# iridia-tam-main-board.net
KiCad netlist of a schematic drawn in EAGLE
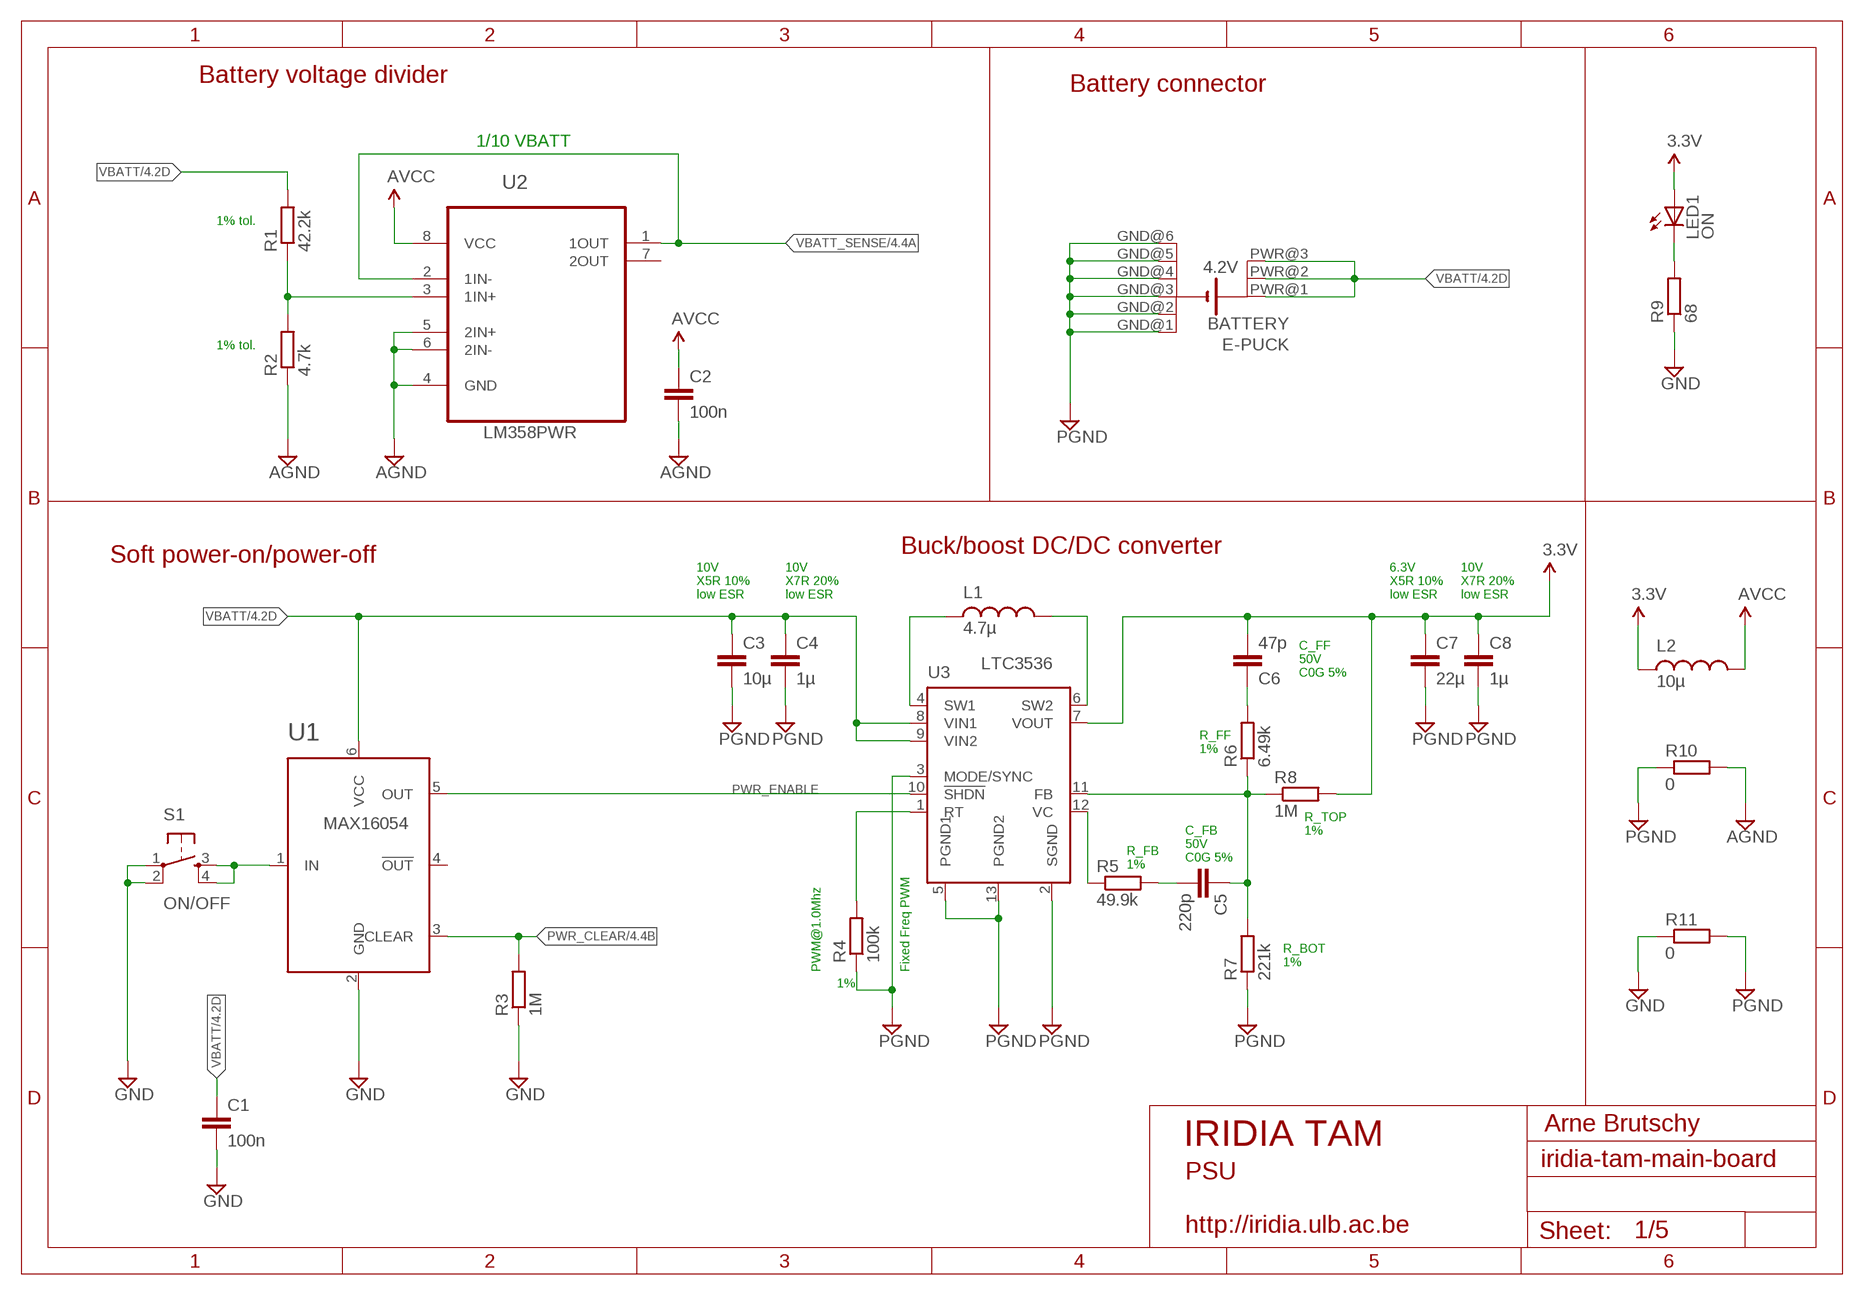
[diagram p0: schematic, sheet 1]
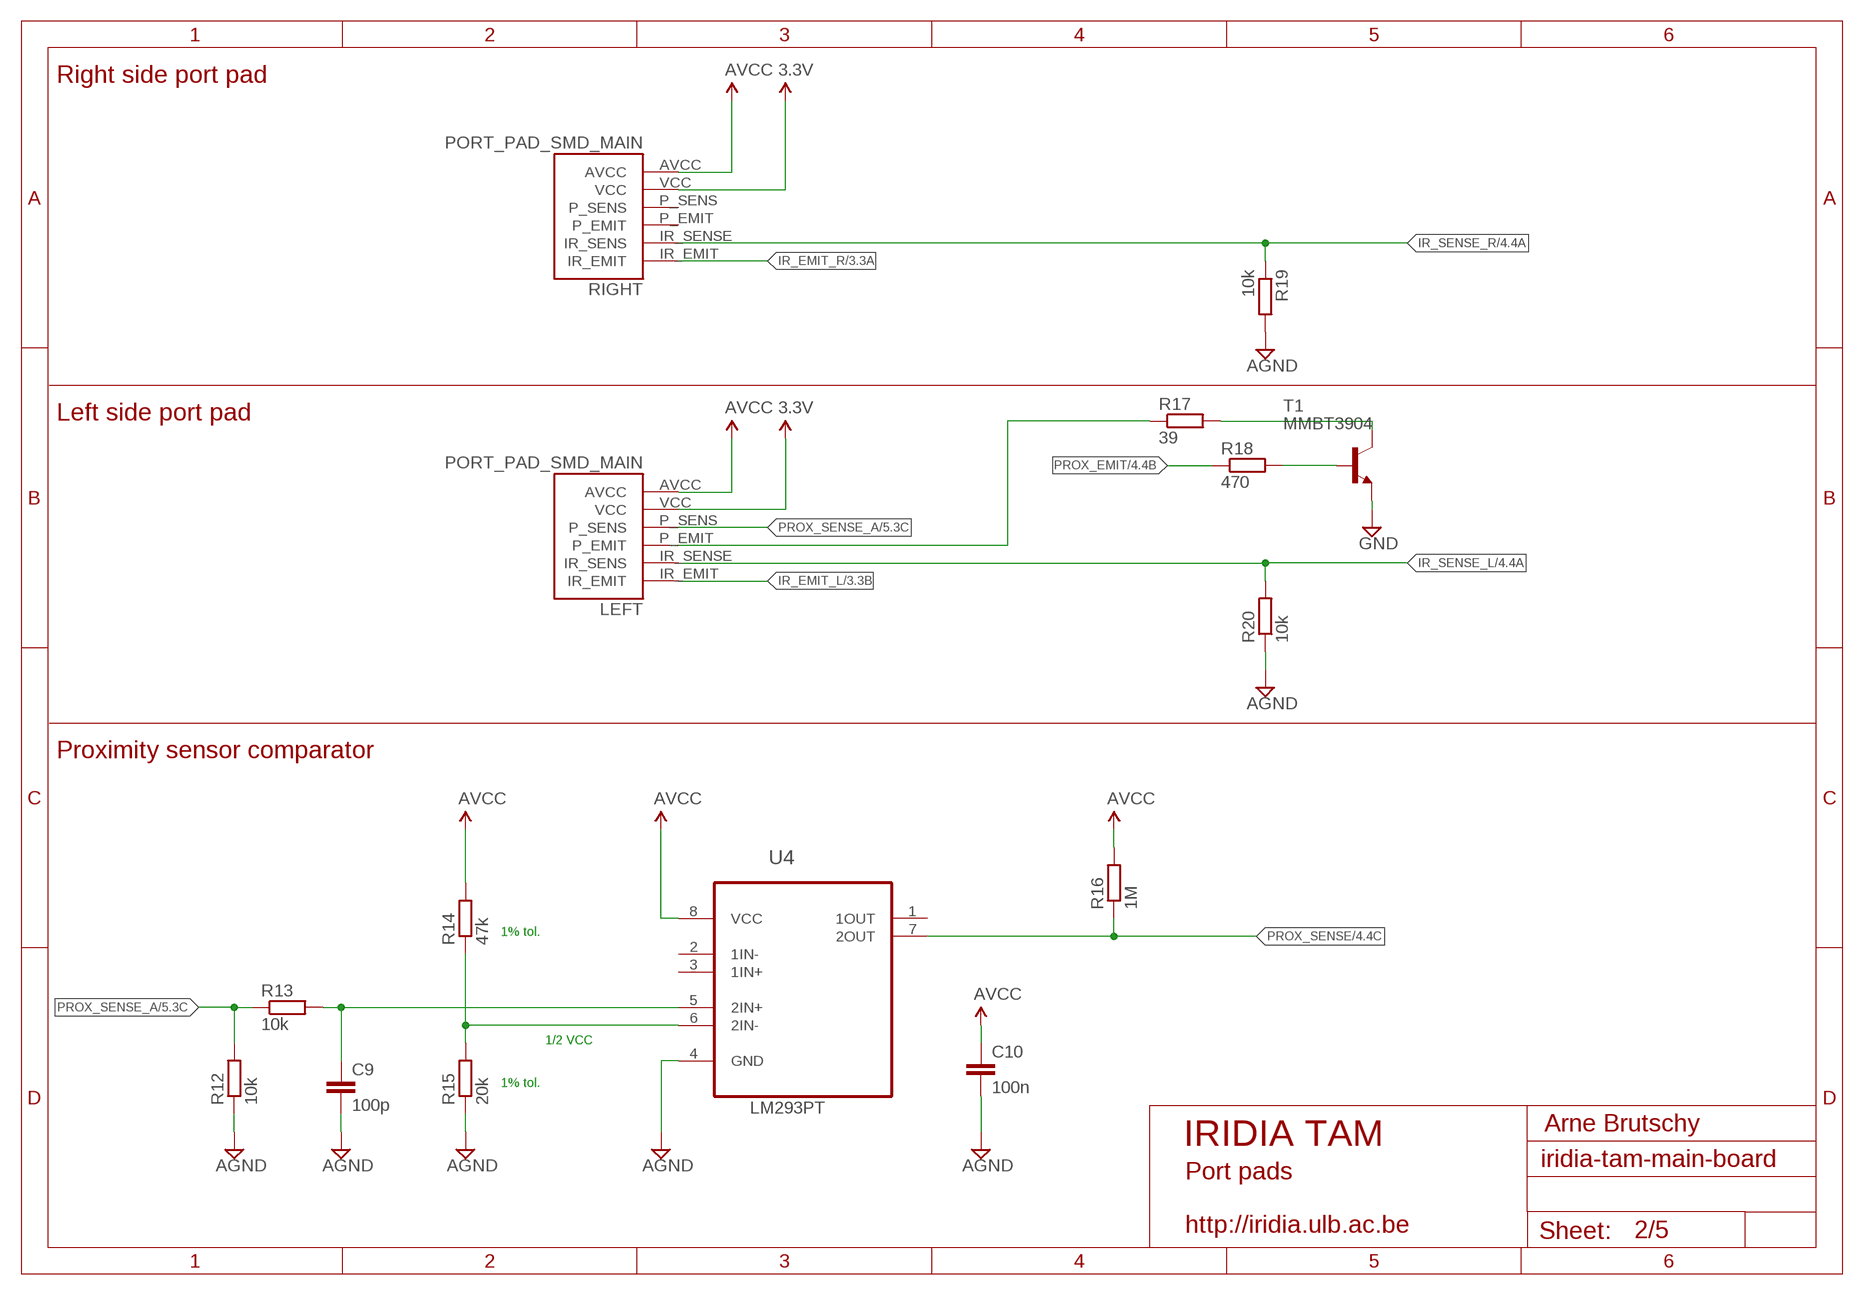
[diagram p1: schematic, sheet 2]
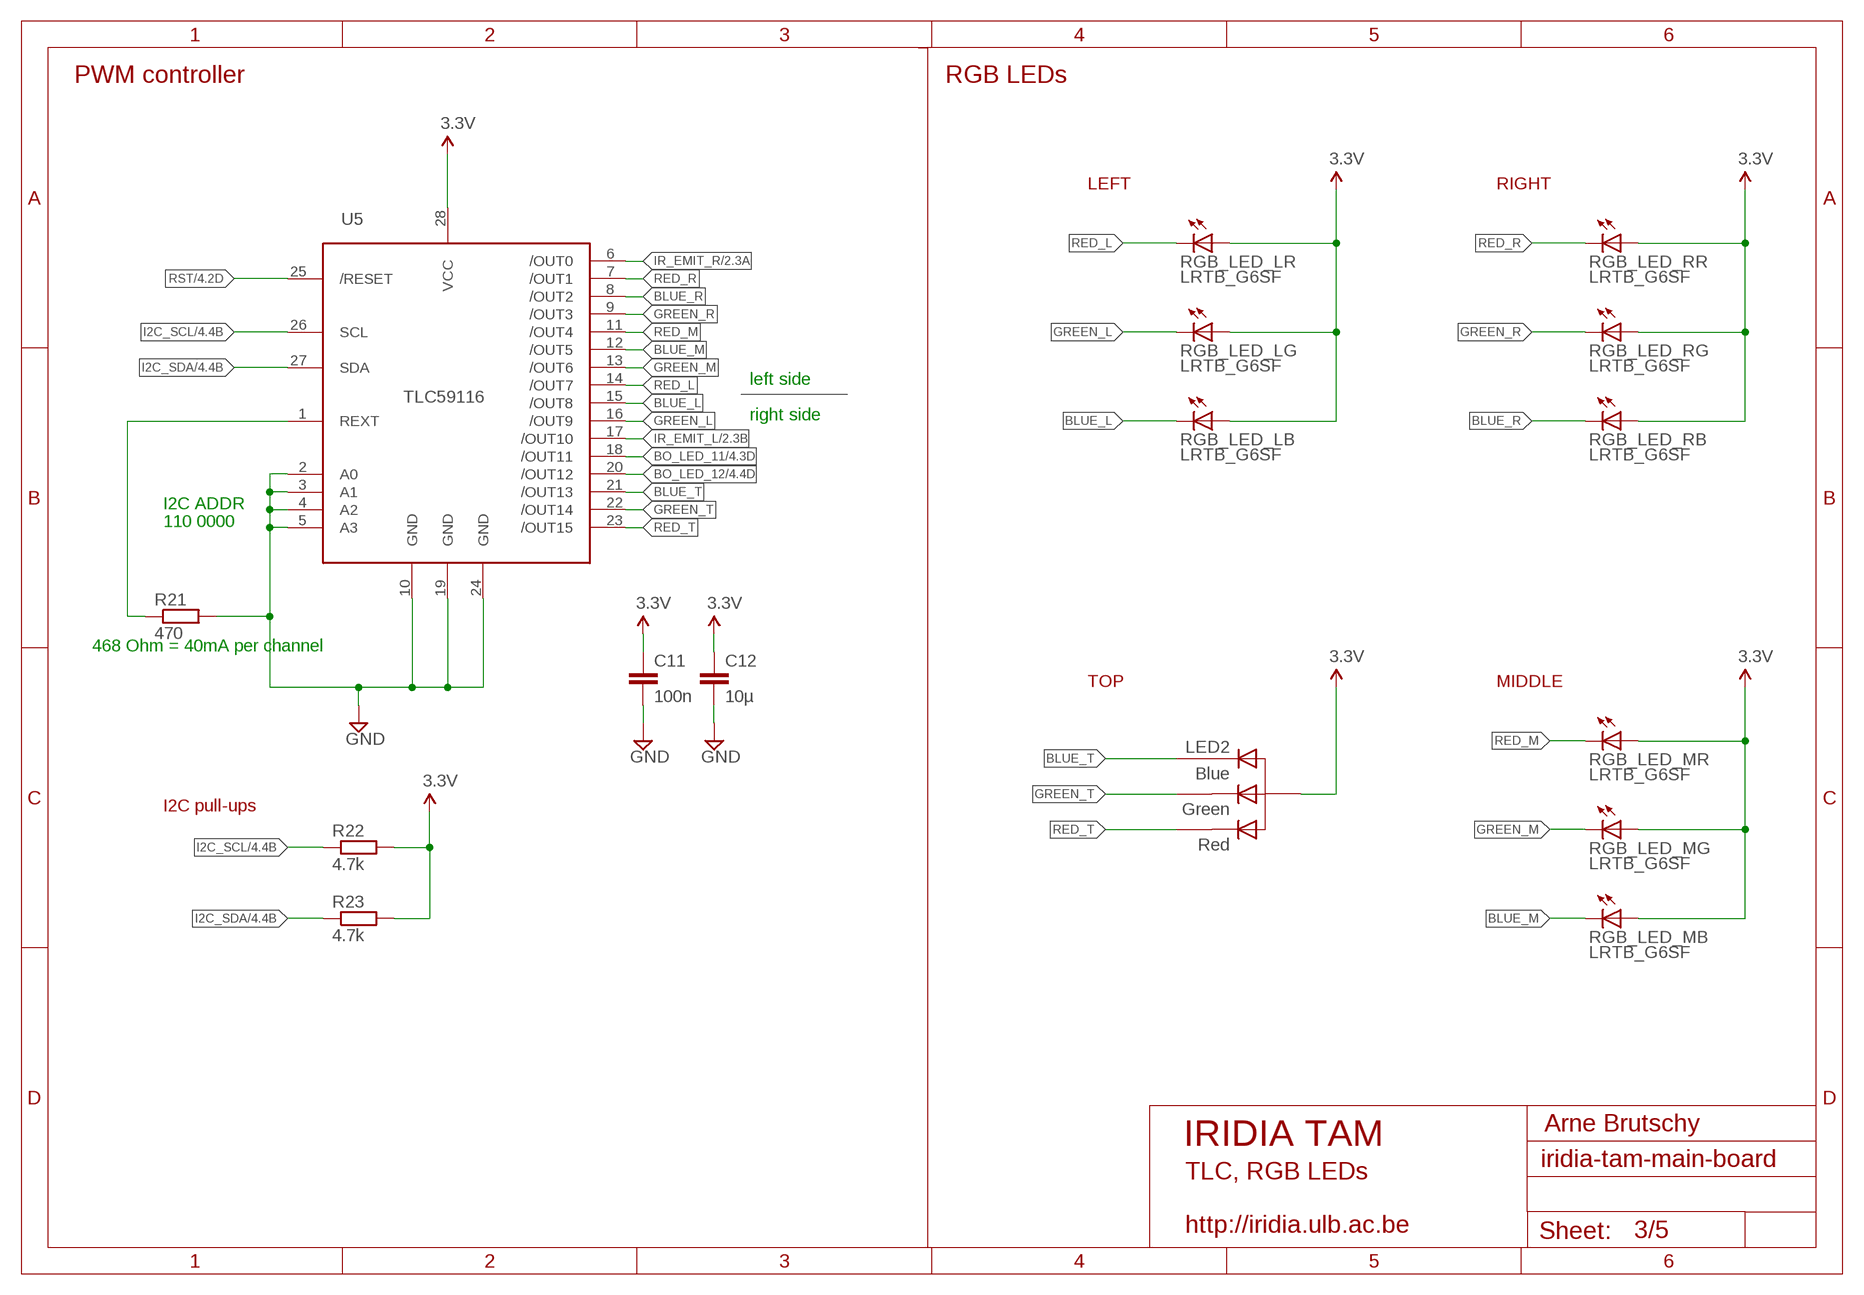
[diagram p2: schematic, sheet 3]
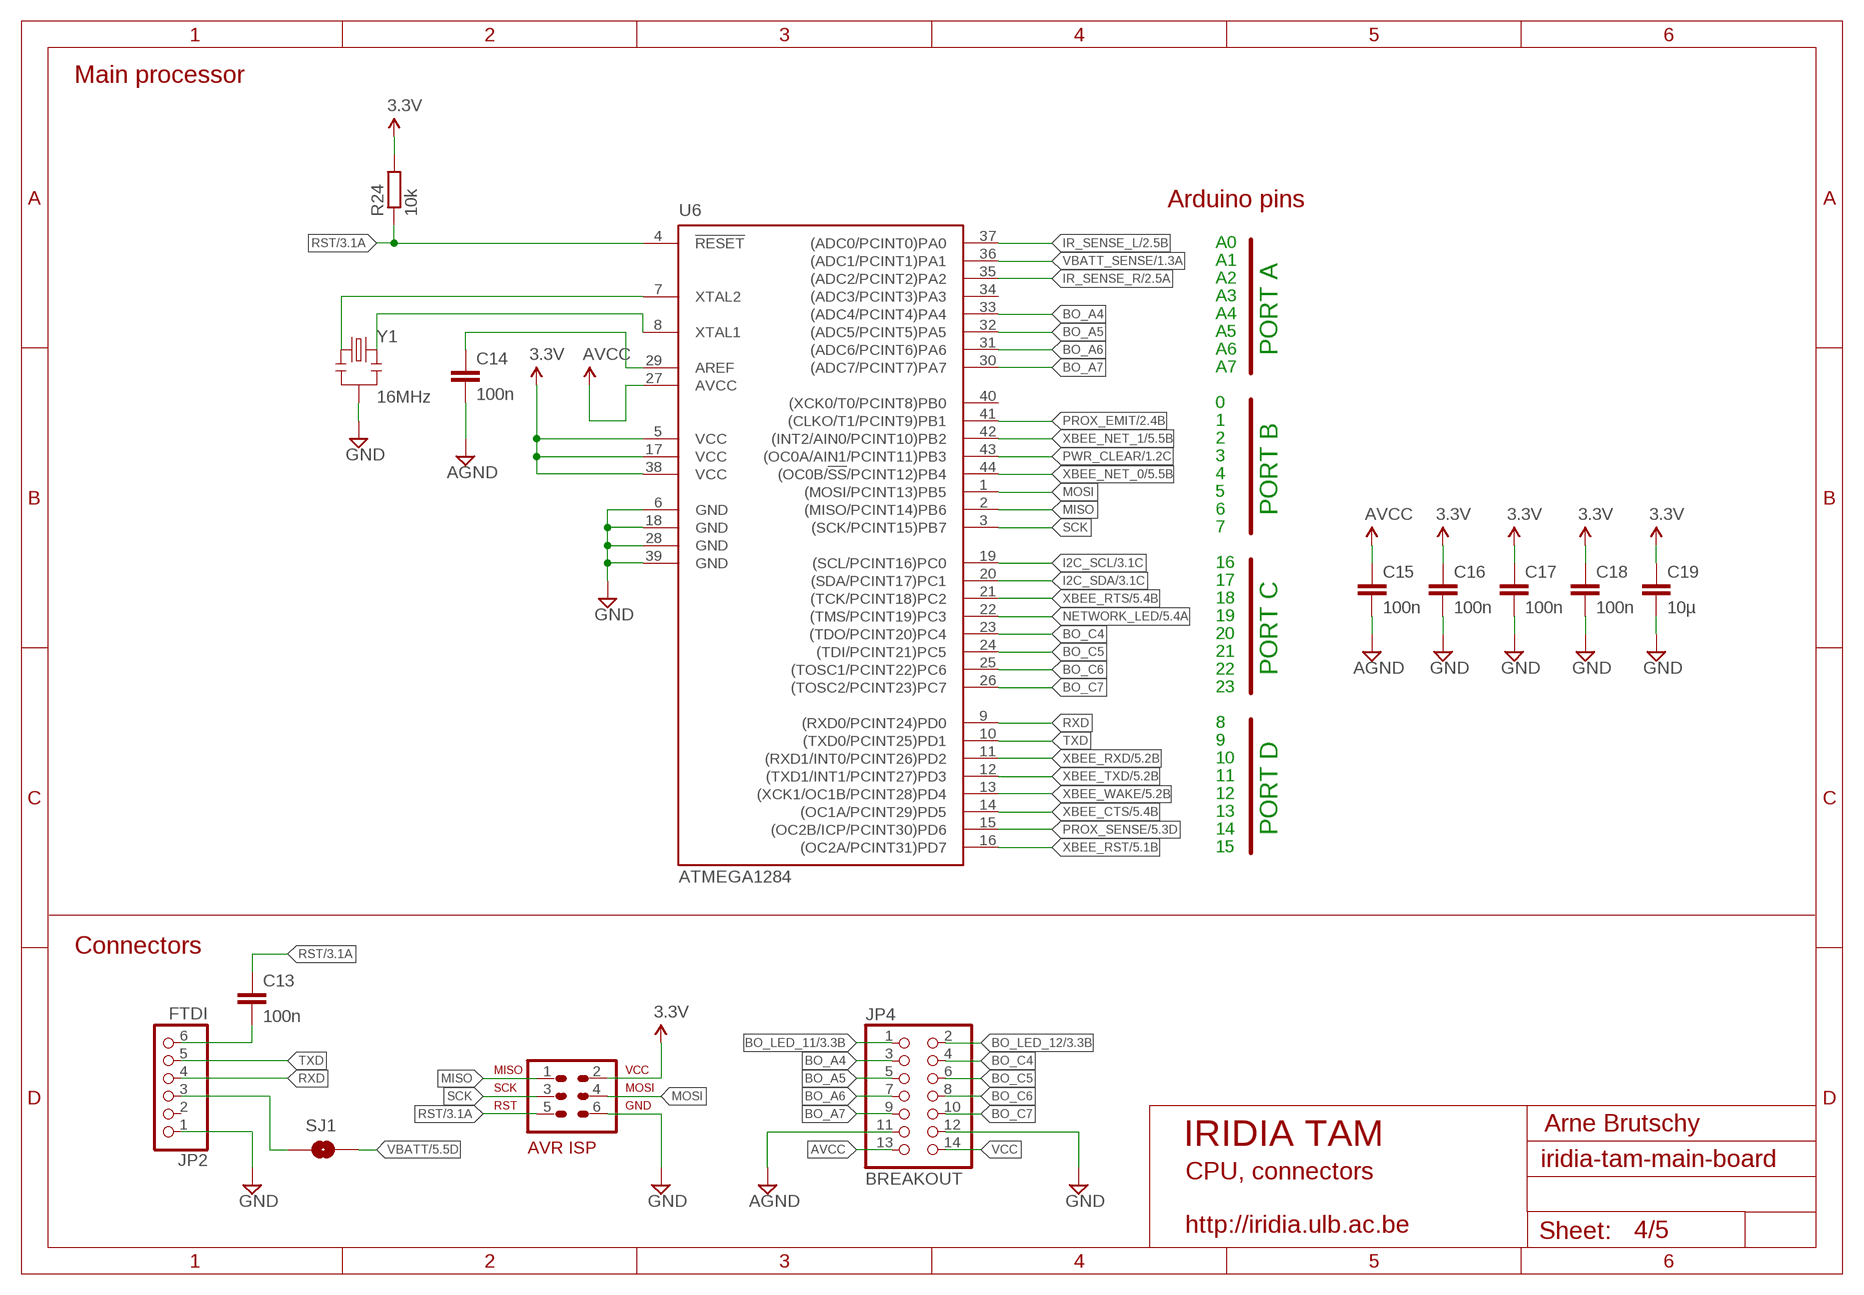
[diagram p3: schematic, sheet 4]
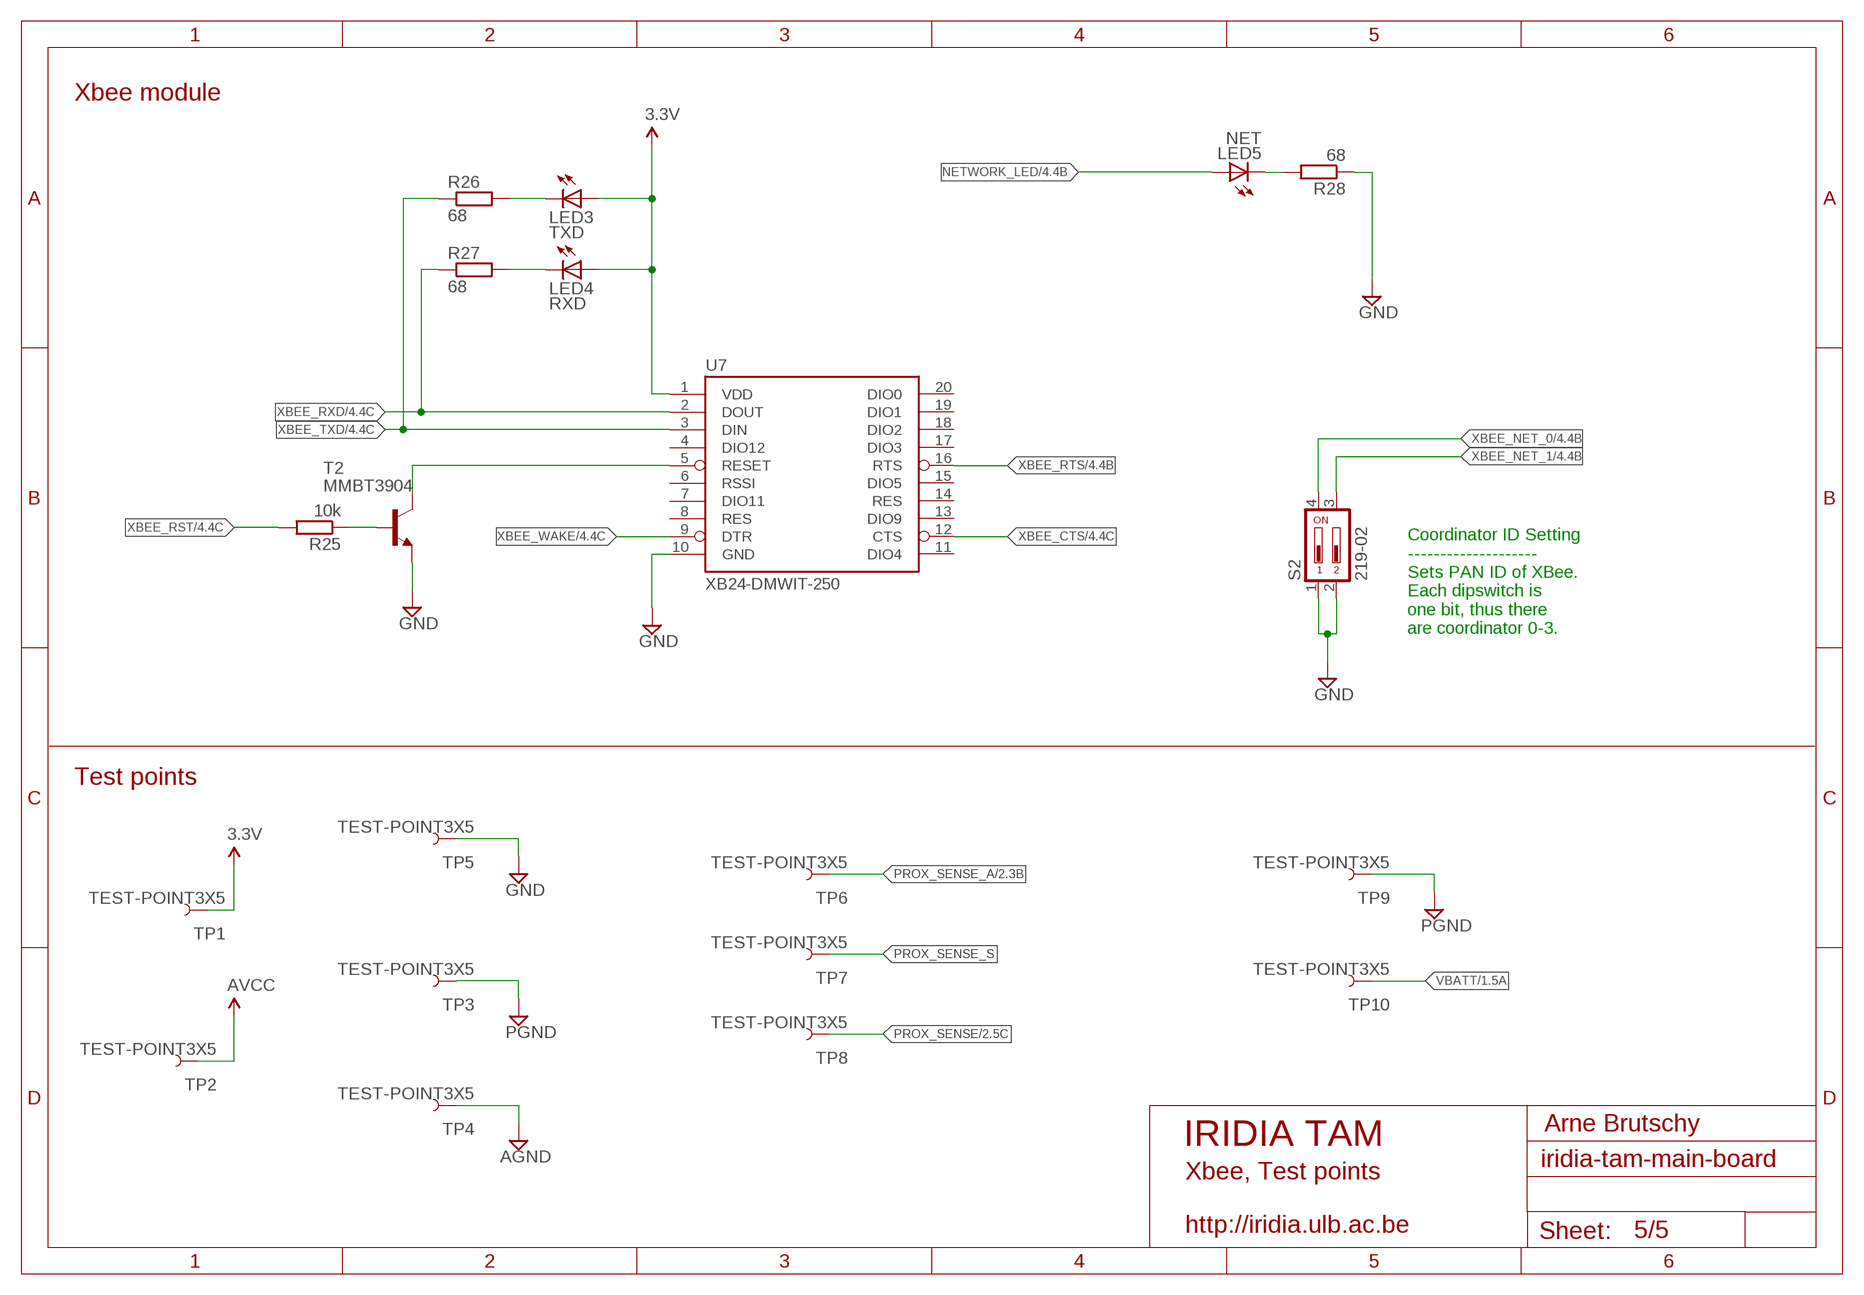
[diagram p4: schematic, sheet 5]

(export (version "E")
  (design (tool "Eeschema 10.0.6"))
  (components
    (comp (ref "C11")
      (value "100n")
      (footprint "eagle-import:C0603")
      (libsource (lib "eagle-import") (part "C-EUC0603"))
    )
    (comp (ref "C12")
      (value "10µ")
      (footprint "eagle-import:C0805")
      (libsource (lib "eagle-import") (part "C-EUC0805"))
    )
    (comp (ref "LED2")
      (value "RGBLED_CA5MMTROUGHHOLE")
      (footprint "eagle-import:LED5MMRGB")
      (libsource (lib "eagle-import") (part "RGBLED_CA5MMTROUGHHOLE"))
    )
    (comp (ref "R21")
      (value "470")
      (footprint "eagle-import:R0603")
      (libsource (lib "eagle-import") (part "R-EU_R0603"))
    )
    (comp (ref "R22")
      (value "4.7k")
      (footprint "eagle-import:R0603")
      (libsource (lib "eagle-import") (part "R-EU_R0603"))
    )
    (comp (ref "R23")
      (value "4.7k")
      (footprint "eagle-import:R0603")
      (libsource (lib "eagle-import") (part "R-EU_R0603"))
    )
    (comp (ref "RGB_LED_L")
      (value "LRTB_G6SF")
      (footprint "eagle-import:P-LCC-6_TOPLED")
      (libsource (lib "eagle-import") (part "MULTILED_LRTB_G6TG"))
    )
    (comp (ref "RGB_LED_M")
      (value "LRTB_G6SF")
      (footprint "eagle-import:P-LCC-6_TOPLED")
      (libsource (lib "eagle-import") (part "MULTILED_LRTB_G6TG"))
    )
    (comp (ref "RGB_LED_R")
      (value "LRTB_G6SF")
      (footprint "eagle-import:P-LCC-6_TOPLED")
      (libsource (lib "eagle-import") (part "MULTILED_LRTB_G6TG"))
    )
    (comp (ref "U5")
      (value "TLC59116-TSSOP")
      (footprint "eagle-import:TSSOP28")
      (libsource (lib "eagle-import") (part "TLC59116-TSSOP"))
    )
    (comp (ref "C9")
      (value "100p")
      (footprint "eagle-import:C0603")
      (libsource (lib "eagle-import") (part "C-EUC0603"))
    )
    (comp (ref "C10")
      (value "100n")
      (footprint "eagle-import:C0603")
      (libsource (lib "eagle-import") (part "C-EUC0603"))
    )
    (comp (ref "LEFT")
      (value "PORT_PAD_SMD_MAIN")
      (footprint "eagle-import:PORT_PAD_SMD_MAIN")
      (libsource (lib "eagle-import") (part "PORT_PAD_SMD_MAIN"))
    )
    (comp (ref "R12")
      (value "10k")
      (footprint "eagle-import:R0603")
      (libsource (lib "eagle-import") (part "R-EU_R0603"))
    )
    (comp (ref "R13")
      (value "10k")
      (footprint "eagle-import:R0603")
      (libsource (lib "eagle-import") (part "R-EU_R0603"))
    )
    (comp (ref "R14")
      (value "47k")
      (footprint "eagle-import:R0603")
      (libsource (lib "eagle-import") (part "R-EU_R0603"))
    )
    (comp (ref "R15")
      (value "20k")
      (footprint "eagle-import:R0603")
      (libsource (lib "eagle-import") (part "R-EU_R0603"))
    )
    (comp (ref "R16")
      (value "1M")
      (footprint "eagle-import:R0603")
      (libsource (lib "eagle-import") (part "R-EU_R0603"))
    )
    (comp (ref "R17")
      (value "39")
      (footprint "eagle-import:R0603")
      (libsource (lib "eagle-import") (part "R-EU_R0603"))
    )
    (comp (ref "R18")
      (value "470")
      (footprint "eagle-import:R0603")
      (libsource (lib "eagle-import") (part "R-EU_R0603"))
    )
    (comp (ref "R19")
      (value "10k")
      (footprint "eagle-import:R0603")
      (libsource (lib "eagle-import") (part "R-EU_R0603"))
    )
    (comp (ref "R20")
      (value "10k")
      (footprint "eagle-import:R0603")
      (libsource (lib "eagle-import") (part "R-EU_R0603"))
    )
    (comp (ref "RIGHT")
      (value "PORT_PAD_SMD_MAIN")
      (footprint "eagle-import:PORT_PAD_SMD_MAIN")
      (libsource (lib "eagle-import") (part "PORT_PAD_SMD_MAIN"))
    )
    (comp (ref "T1")
      (value "MMBT3904")
      (footprint "eagle-import:SOT23-BEC")
      (libsource (lib "eagle-import") (part "-NPN-SOT23-BECMMBT3904LT1"))
    )
    (comp (ref "U4")
      (value "LM293PT")
      (footprint "eagle-import:8-TSSOP_4.4MM")
      (libsource (lib "eagle-import") (part "LM293PT"))
    )
    (comp (ref "C13")
      (value "100n")
      (footprint "eagle-import:C0603")
      (libsource (lib "eagle-import") (part "C-EUC0603"))
    )
    (comp (ref "C14")
      (value "100n")
      (footprint "eagle-import:C0603")
      (libsource (lib "eagle-import") (part "C-EUC0603"))
    )
    (comp (ref "C15")
      (value "100n")
      (footprint "eagle-import:C0603")
      (libsource (lib "eagle-import") (part "C-EUC0603"))
    )
    (comp (ref "C16")
      (value "100n")
      (footprint "eagle-import:C0603")
      (libsource (lib "eagle-import") (part "C-EUC0603"))
    )
    (comp (ref "C17")
      (value "100n")
      (footprint "eagle-import:C0603")
      (libsource (lib "eagle-import") (part "C-EUC0603"))
    )
    (comp (ref "C18")
      (value "100n")
      (footprint "eagle-import:C0603")
      (libsource (lib "eagle-import") (part "C-EUC0603"))
    )
    (comp (ref "C19")
      (value "10µ")
      (footprint "eagle-import:C0805")
      (libsource (lib "eagle-import") (part "C-EUC0805"))
    )
    (comp (ref "JP2")
      (value "FTDI")
      (footprint "eagle-import:1X06SMD_90")
      (libsource (lib "eagle-import") (part "PINHD-1X6_2.54-SMD-90°"))
    )
    (comp (ref "JP3")
      (value "ISP")
      (footprint "eagle-import:AVR-ISP-6")
      (libsource (lib "eagle-import") (part "AVR-ISP-6VERT"))
    )
    (comp (ref "JP4")
      (value "BREAKOUT")
      (footprint "eagle-import:2X07SMD")
      (libsource (lib "eagle-import") (part "PINHD-2X07_2.54-SMD"))
    )
    (comp (ref "R24")
      (value "10k")
      (footprint "eagle-import:R0603")
      (libsource (lib "eagle-import") (part "R-EU_R0603"))
    )
    (comp (ref "SJ1")
      (value "SOLDERJUMPERTRACE")
      (footprint "eagle-import:SJ_2S-TRACE")
      (libsource (lib "eagle-import") (part "SOLDERJUMPERTRACE"))
    )
    (comp (ref "U6")
      (value "ATMEGA1284")
      (footprint "eagle-import:TQFP44")
      (libsource (lib "eagle-import") (part "ATMEGA164/324/644/1284-AU"))
    )
    (comp (ref "Y1")
      (value "16MHz")
      (footprint "eagle-import:RESONATOR-SMD")
      (libsource (lib "eagle-import") (part "RESONATOR16MHZ"))
    )
    (comp (ref "C1")
      (value "100n")
      (footprint "eagle-import:C0603")
      (libsource (lib "eagle-import") (part "C-EUC0603"))
    )
    (comp (ref "C2")
      (value "100n")
      (footprint "eagle-import:C0603")
      (libsource (lib "eagle-import") (part "C-EUC0603"))
    )
    (comp (ref "C3")
      (value "10µ")
      (footprint "eagle-import:C0805")
      (libsource (lib "eagle-import") (part "C-EUC0805"))
    )
    (comp (ref "C4")
      (value "1µ")
      (footprint "eagle-import:C0603")
      (libsource (lib "eagle-import") (part "C-EUC0603"))
    )
    (comp (ref "C5")
      (value "220p")
      (footprint "eagle-import:C0603")
      (libsource (lib "eagle-import") (part "C-EUC0603"))
    )
    (comp (ref "C6")
      (value "47p")
      (footprint "eagle-import:C0603")
      (libsource (lib "eagle-import") (part "C-EUC0603"))
    )
    (comp (ref "C7")
      (value "22µ")
      (footprint "eagle-import:C1206")
      (libsource (lib "eagle-import") (part "C-EUC1206"))
    )
    (comp (ref "C8")
      (value "1µ")
      (footprint "eagle-import:C0603")
      (libsource (lib "eagle-import") (part "C-EUC0603"))
    )
    (comp (ref "JP1")
      (value "EPUCK_BATTERY")
      (footprint "eagle-import:EPUCK_BATTERY")
      (libsource (lib "eagle-import") (part "EPUCK_BATTERY"))
    )
    (comp (ref "L1")
      (value "4.7µ")
      (footprint "eagle-import:TDK-VLCF")
      (libsource (lib "eagle-import") (part "TDK-INDUCTORS-VLCF"))
    )
    (comp (ref "L2")
      (value "10µ")
      (footprint "eagle-import:L0805")
      (libsource (lib "eagle-import") (part "0805-INDUCTORS"))
    )
    (comp (ref "LED1")
      (value "ON")
      (footprint "eagle-import:CHIPLED_1206")
      (libsource (lib "eagle-import") (part "LEDCHIPLED_1206"))
    )
    (comp (ref "R1")
      (value "42.2k")
      (footprint "eagle-import:R0603")
      (libsource (lib "eagle-import") (part "R-EU_R0603"))
    )
    (comp (ref "R2")
      (value "4.7k")
      (footprint "eagle-import:R0603")
      (libsource (lib "eagle-import") (part "R-EU_R0603"))
    )
    (comp (ref "R3")
      (value "1M")
      (footprint "eagle-import:R0603")
      (libsource (lib "eagle-import") (part "R-EU_R0603"))
    )
    (comp (ref "R4")
      (value "100k")
      (footprint "eagle-import:R0603")
      (libsource (lib "eagle-import") (part "R-EU_R0603"))
    )
    (comp (ref "R5")
      (value "49.9k")
      (footprint "eagle-import:R0603")
      (libsource (lib "eagle-import") (part "R-EU_R0603"))
    )
    (comp (ref "R6")
      (value "6.49k")
      (footprint "eagle-import:R0603")
      (libsource (lib "eagle-import") (part "R-EU_R0603"))
    )
    (comp (ref "R7")
      (value "221k")
      (footprint "eagle-import:R0603")
      (libsource (lib "eagle-import") (part "R-EU_R0603"))
    )
    (comp (ref "R8")
      (value "1M")
      (footprint "eagle-import:R0603")
      (libsource (lib "eagle-import") (part "R-EU_R0603"))
    )
    (comp (ref "R9")
      (value "68")
      (footprint "eagle-import:R0603")
      (libsource (lib "eagle-import") (part "R-EU_R0603"))
    )
    (comp (ref "R10")
      (value "0")
      (footprint "eagle-import:R0603")
      (libsource (lib "eagle-import") (part "R-EU_R0603"))
    )
    (comp (ref "R11")
      (value "0")
      (footprint "eagle-import:R0603")
      (libsource (lib "eagle-import") (part "R-EU_R0603"))
    )
    (comp (ref "S1")
      (value "ON/OFF")
      (footprint "eagle-import:TACTILE_SWITCH_SMD")
      (libsource (lib "eagle-import") (part "TAC_SWITCHSMD"))
    )
    (comp (ref "U1")
      (value "MAX16054")
      (footprint "eagle-import:SOT23-6-INV")
      (libsource (lib "eagle-import") (part "MAX16054"))
    )
    (comp (ref "U2")
      (value "LM358PW")
      (footprint "eagle-import:SOP65P640X120-8N")
      (libsource (lib "eagle-import") (part "LM358PW"))
    )
    (comp (ref "U3")
      (value "LTC3536")
      (footprint "eagle-import:MSOP12-EP")
      (libsource (lib "eagle-import") (part "LTC3536"))
    )
    (comp (ref "LED3")
      (value "TXD")
      (footprint "eagle-import:CHIPLED_0805")
      (libsource (lib "eagle-import") (part "LEDCHIPLED_0805"))
    )
    (comp (ref "LED4")
      (value "RXD")
      (footprint "eagle-import:CHIPLED_0805")
      (libsource (lib "eagle-import") (part "LEDCHIPLED_0805"))
    )
    (comp (ref "LED5")
      (value "NET")
      (footprint "eagle-import:CHIPLED_0805")
      (libsource (lib "eagle-import") (part "LEDCHIPLED_0805"))
    )
    (comp (ref "R25")
      (value "10k")
      (footprint "eagle-import:R0603")
      (libsource (lib "eagle-import") (part "R-EU_R0603"))
    )
    (comp (ref "R26")
      (value "68")
      (footprint "eagle-import:R0603")
      (libsource (lib "eagle-import") (part "R-EU_R0603"))
    )
    (comp (ref "R27")
      (value "68")
      (footprint "eagle-import:R0603")
      (libsource (lib "eagle-import") (part "R-EU_R0603"))
    )
    (comp (ref "R28")
      (value "68")
      (footprint "eagle-import:R0603")
      (libsource (lib "eagle-import") (part "R-EU_R0603"))
    )
    (comp (ref "S2")
      (value "219-02")
      (footprint "eagle-import:CTS-219-02")
      (libsource (lib "eagle-import") (part "219-02"))
    )
    (comp (ref "T2")
      (value "MMBT3904")
      (footprint "eagle-import:SOT23-BEC")
      (libsource (lib "eagle-import") (part "-NPN-SOT23-BECMMBT3904LT1"))
    )
    (comp (ref "TP1")
      (value "TEST-POINT3X5")
      (footprint "eagle-import:PAD.03X.05")
      (libsource (lib "eagle-import") (part "TEST-POINT3X5"))
    )
    (comp (ref "TP2")
      (value "TEST-POINT3X5")
      (footprint "eagle-import:PAD.03X.05")
      (libsource (lib "eagle-import") (part "TEST-POINT3X5"))
    )
    (comp (ref "TP3")
      (value "TEST-POINT3X5")
      (footprint "eagle-import:PAD.03X.05")
      (libsource (lib "eagle-import") (part "TEST-POINT3X5"))
    )
    (comp (ref "TP4")
      (value "TEST-POINT3X5")
      (footprint "eagle-import:PAD.03X.05")
      (libsource (lib "eagle-import") (part "TEST-POINT3X5"))
    )
    (comp (ref "TP5")
      (value "TEST-POINT3X5")
      (footprint "eagle-import:PAD.03X.05")
      (libsource (lib "eagle-import") (part "TEST-POINT3X5"))
    )
    (comp (ref "TP6")
      (value "TEST-POINT3X5")
      (footprint "eagle-import:PAD.03X.05")
      (libsource (lib "eagle-import") (part "TEST-POINT3X5"))
    )
    (comp (ref "TP7")
      (value "TEST-POINT3X5")
      (footprint "eagle-import:PAD.03X.05")
      (libsource (lib "eagle-import") (part "TEST-POINT3X5"))
    )
    (comp (ref "TP8")
      (value "TEST-POINT3X5")
      (footprint "eagle-import:PAD.03X.05")
      (libsource (lib "eagle-import") (part "TEST-POINT3X5"))
    )
    (comp (ref "TP9")
      (value "TEST-POINT3X5")
      (footprint "eagle-import:PAD.03X.05")
      (libsource (lib "eagle-import") (part "TEST-POINT3X5"))
    )
    (comp (ref "TP10")
      (value "TEST-POINT3X5")
      (footprint "eagle-import:PAD.03X.05")
      (libsource (lib "eagle-import") (part "TEST-POINT3X5"))
    )
    (comp (ref "U7")
      (value "XB24-DMWIT-250")
      (footprint "eagle-import:XBEE-SMD")
      (libsource (lib "eagle-import") (part "XBEE-1B3"))
    )
  )
  (nets
    (net (code "1") (name "AGND") (class "Default")
      (node (ref "C10") (pin "2") (pinfunction "2_2") (pintype "passive"))
      (node (ref "C14") (pin "2") (pinfunction "2_2") (pintype "passive"))
      (node (ref "C15") (pin "2") (pinfunction "2_2") (pintype "passive"))
      (node (ref "C2") (pin "2") (pinfunction "2_2") (pintype "passive"))
      (node (ref "C9") (pin "2") (pinfunction "2_2") (pintype "passive"))
      (node (ref "JP4") (pin "11") (pinfunction "11_11") (pintype "passive"))
      (node (ref "R10") (pin "2") (pinfunction "2_2") (pintype "passive"))
      (node (ref "R12") (pin "1") (pinfunction "1_1") (pintype "passive"))
      (node (ref "R15") (pin "1") (pinfunction "1_1") (pintype "passive"))
      (node (ref "R19") (pin "2") (pinfunction "2_2") (pintype "passive"))
      (node (ref "R2") (pin "1") (pinfunction "1_1") (pintype "passive"))
      (node (ref "R20") (pin "1") (pinfunction "1_1") (pintype "passive"))
      (node (ref "TP4") (pin "P$1") (pinfunction "1_P$1") (pintype "bidirectional"))
      (node (ref "U2") (pin "4") (pinfunction "GND_4") (pintype "passive"))
      (node (ref "U2") (pin "5") (pinfunction "2IN+_5") (pintype "input"))
      (node (ref "U2") (pin "6") (pinfunction "2IN-_6") (pintype "input"))
      (node (ref "U4") (pin "4") (pinfunction "GND_4") (pintype "passive"))
    )
    (net (code "2") (name "AVCC") (class "Default")
      (node (ref "C10") (pin "1") (pinfunction "1_1") (pintype "passive"))
      (node (ref "C15") (pin "1") (pinfunction "1_1") (pintype "passive"))
      (node (ref "C2") (pin "1") (pinfunction "1_1") (pintype "passive"))
      (node (ref "JP4") (pin "13") (pinfunction "13_13") (pintype "passive"))
      (node (ref "L2") (pin "2") (pinfunction "P$2_2") (pintype "passive"))
      (node (ref "LEFT") (pin "AVCC") (pinfunction "AVCC_AVCC") (pintype "bidirectional"))
      (node (ref "R14") (pin "2") (pinfunction "2_2") (pintype "passive"))
      (node (ref "R16") (pin "2") (pinfunction "2_2") (pintype "passive"))
      (node (ref "RIGHT") (pin "AVCC") (pinfunction "AVCC_AVCC") (pintype "bidirectional"))
      (node (ref "TP2") (pin "P$1") (pinfunction "1_P$1") (pintype "bidirectional"))
      (node (ref "U2") (pin "8") (pinfunction "VCC_8") (pintype "power_in"))
      (node (ref "U4") (pin "8") (pinfunction "VCC_8") (pintype "power_in"))
      (node (ref "U6") (pin "27") (pinfunction "AVCC_27") (pintype "power_in"))
    )
    (net (code "3") (name "BLUE_L") (class "Default")
      (node (ref "RGB_LED_L") (pin "C3") (pinfunction "C_C3") (pintype "passive"))
      (node (ref "U5") (pin "15") (pinfunction "/OUT8_15") (pintype "bidirectional"))
    )
    (net (code "4") (name "BLUE_M") (class "Default")
      (node (ref "RGB_LED_M") (pin "C3") (pinfunction "C_C3") (pintype "passive"))
      (node (ref "U5") (pin "12") (pinfunction "/OUT5_12") (pintype "bidirectional"))
    )
    (net (code "5") (name "BLUE_R") (class "Default")
      (node (ref "RGB_LED_R") (pin "C3") (pinfunction "C_C3") (pintype "passive"))
      (node (ref "U5") (pin "8") (pinfunction "/OUT2_8") (pintype "bidirectional"))
    )
    (net (code "6") (name "BLUE_T") (class "Default")
      (node (ref "LED2") (pin "4") (pinfunction "CB_4") (pintype "bidirectional"))
      (node (ref "U5") (pin "21") (pinfunction "/OUT13_21") (pintype "bidirectional"))
    )
    (net (code "7") (name "BO_A4") (class "Default")
      (node (ref "JP4") (pin "3") (pinfunction "3_3") (pintype "passive"))
      (node (ref "U6") (pin "33") (pinfunction "(ADC4/PCINT4)PA4_33") (pintype "bidirectional"))
    )
    (net (code "8") (name "BO_A5") (class "Default")
      (node (ref "JP4") (pin "5") (pinfunction "5_5") (pintype "passive"))
      (node (ref "U6") (pin "32") (pinfunction "(ADC5/PCINT5)PA5_32") (pintype "bidirectional"))
    )
    (net (code "9") (name "BO_A6") (class "Default")
      (node (ref "JP4") (pin "7") (pinfunction "7_7") (pintype "passive"))
      (node (ref "U6") (pin "31") (pinfunction "(ADC6/PCINT6)PA6_31") (pintype "bidirectional"))
    )
    (net (code "10") (name "BO_A7") (class "Default")
      (node (ref "JP4") (pin "9") (pinfunction "9_9") (pintype "passive"))
      (node (ref "U6") (pin "30") (pinfunction "(ADC7/PCINT7)PA7_30") (pintype "bidirectional"))
    )
    (net (code "11") (name "BO_C4") (class "Default")
      (node (ref "JP4") (pin "4") (pinfunction "4_4") (pintype "passive"))
      (node (ref "U6") (pin "23") (pinfunction "(TDO/PCINT20)PC4_23") (pintype "bidirectional"))
    )
    (net (code "12") (name "BO_C5") (class "Default")
      (node (ref "JP4") (pin "6") (pinfunction "6_6") (pintype "passive"))
      (node (ref "U6") (pin "24") (pinfunction "(TDI/PCINT21)PC5_24") (pintype "bidirectional"))
    )
    (net (code "13") (name "BO_C6") (class "Default")
      (node (ref "JP4") (pin "8") (pinfunction "8_8") (pintype "passive"))
      (node (ref "U6") (pin "25") (pinfunction "(TOSC1/PCINT22)PC6_25") (pintype "bidirectional"))
    )
    (net (code "14") (name "BO_C7") (class "Default")
      (node (ref "JP4") (pin "10") (pinfunction "10_10") (pintype "passive"))
      (node (ref "U6") (pin "26") (pinfunction "(TOSC2/PCINT23)PC7_26") (pintype "bidirectional"))
    )
    (net (code "15") (name "BO_LED_11") (class "Default")
      (node (ref "JP4") (pin "1") (pinfunction "1_1") (pintype "passive"))
      (node (ref "U5") (pin "18") (pinfunction "/OUT11_18") (pintype "bidirectional"))
    )
    (net (code "16") (name "BO_LED_12") (class "Default")
      (node (ref "JP4") (pin "2") (pinfunction "2_2") (pintype "passive"))
      (node (ref "U5") (pin "20") (pinfunction "/OUT12_20") (pintype "bidirectional"))
    )
    (net (code "17") (name "GND") (class "Default")
      (node (ref "C1") (pin "2") (pinfunction "2_2") (pintype "passive"))
      (node (ref "C11") (pin "2") (pinfunction "2_2") (pintype "passive"))
      (node (ref "C12") (pin "2") (pinfunction "2_2") (pintype "passive"))
      (node (ref "C16") (pin "2") (pinfunction "2_2") (pintype "passive"))
      (node (ref "C17") (pin "2") (pinfunction "2_2") (pintype "passive"))
      (node (ref "C18") (pin "2") (pinfunction "2_2") (pintype "passive"))
      (node (ref "C19") (pin "2") (pinfunction "2_2") (pintype "passive"))
      (node (ref "JP2") (pin "1") (pinfunction "1_1") (pintype "passive"))
      (node (ref "JP3") (pin "6") (pinfunction "6_6") (pintype "passive"))
      (node (ref "JP4") (pin "12") (pinfunction "12_12") (pintype "passive"))
      (node (ref "R11") (pin "1") (pinfunction "1_1") (pintype "passive"))
      (node (ref "R21") (pin "2") (pinfunction "2_2") (pintype "passive"))
      (node (ref "R28") (pin "1") (pinfunction "1_1") (pintype "passive"))
      (node (ref "R3") (pin "1") (pinfunction "1_1") (pintype "passive"))
      (node (ref "R9") (pin "1") (pinfunction "1_1") (pintype "passive"))
      (node (ref "S1") (pin "1") (pinfunction "1_1") (pintype "passive"))
      (node (ref "S1") (pin "2") (pinfunction "2_2") (pintype "passive"))
      (node (ref "S2") (pin "1") (pinfunction "1_1") (pintype "passive"))
      (node (ref "S2") (pin "2") (pinfunction "2_2") (pintype "passive"))
      (node (ref "T1") (pin "E") (pinfunction "E_E") (pintype "passive"))
      (node (ref "T2") (pin "E") (pinfunction "E_E") (pintype "passive"))
      (node (ref "TP5") (pin "P$1") (pinfunction "1_P$1") (pintype "bidirectional"))
      (node (ref "U1") (pin "2") (pinfunction "GND_2") (pintype "power_in"))
      (node (ref "U5") (pin "10") (pinfunction "GND_10") (pintype "bidirectional"))
      (node (ref "U5") (pin "19") (pinfunction "GND_19") (pintype "bidirectional"))
      (node (ref "U5") (pin "2") (pinfunction "A0_2") (pintype "bidirectional"))
      (node (ref "U5") (pin "24") (pinfunction "GND_24") (pintype "bidirectional"))
      (node (ref "U5") (pin "3") (pinfunction "A1_3") (pintype "bidirectional"))
      (node (ref "U5") (pin "4") (pinfunction "A2_4") (pintype "bidirectional"))
      (node (ref "U5") (pin "5") (pinfunction "A3_5") (pintype "bidirectional"))
      (node (ref "U6") (pin "18") (pinfunction "GND_18") (pintype "power_in"))
      (node (ref "U6") (pin "28") (pinfunction "GND_28") (pintype "power_in"))
      (node (ref "U6") (pin "39") (pinfunction "GND_39") (pintype "power_in"))
      (node (ref "U6") (pin "6") (pinfunction "GND_6") (pintype "power_in"))
      (node (ref "U7") (pin "10") (pinfunction "GND_10") (pintype "power_in"))
      (node (ref "Y1") (pin "2") (pinfunction "2_2") (pintype "passive"))
    )
    (net (code "18") (name "GREEN_L") (class "Default")
      (node (ref "RGB_LED_L") (pin "C2") (pinfunction "C_C2") (pintype "passive"))
      (node (ref "U5") (pin "16") (pinfunction "/OUT9_16") (pintype "bidirectional"))
    )
    (net (code "19") (name "GREEN_M") (class "Default")
      (node (ref "RGB_LED_M") (pin "C2") (pinfunction "C_C2") (pintype "passive"))
      (node (ref "U5") (pin "13") (pinfunction "/OUT6_13") (pintype "bidirectional"))
    )
    (net (code "20") (name "GREEN_R") (class "Default")
      (node (ref "RGB_LED_R") (pin "C2") (pinfunction "C_C2") (pintype "passive"))
      (node (ref "U5") (pin "9") (pinfunction "/OUT3_9") (pintype "bidirectional"))
    )
    (net (code "21") (name "GREEN_T") (class "Default")
      (node (ref "LED2") (pin "3") (pinfunction "CG_3") (pintype "bidirectional"))
      (node (ref "U5") (pin "22") (pinfunction "/OUT14_22") (pintype "bidirectional"))
    )
    (net (code "22") (name "I2C_SCL") (class "Default")
      (node (ref "R22") (pin "1") (pinfunction "1_1") (pintype "passive"))
      (node (ref "U5") (pin "26") (pinfunction "SCL_26") (pintype "bidirectional"))
      (node (ref "U6") (pin "19") (pinfunction "(SCL/PCINT16)PC0_19") (pintype "bidirectional"))
    )
    (net (code "23") (name "I2C_SDA") (class "Default")
      (node (ref "R23") (pin "1") (pinfunction "1_1") (pintype "passive"))
      (node (ref "U5") (pin "27") (pinfunction "SDA_27") (pintype "bidirectional"))
      (node (ref "U6") (pin "20") (pinfunction "(SDA/PCINT17)PC1_20") (pintype "bidirectional"))
    )
    (net (code "24") (name "IR_EMIT_L") (class "Default")
      (node (ref "LEFT") (pin "IR_EMIT") (pinfunction "IR_EMIT_IR_EMIT") (pintype "bidirectional"))
      (node (ref "U5") (pin "17") (pinfunction "/OUT10_17") (pintype "bidirectional"))
    )
    (net (code "25") (name "IR_EMIT_R") (class "Default")
      (node (ref "RIGHT") (pin "IR_EMIT") (pinfunction "IR_EMIT_IR_EMIT") (pintype "bidirectional"))
      (node (ref "U5") (pin "6") (pinfunction "/OUT0_6") (pintype "bidirectional"))
    )
    (net (code "26") (name "IR_SENSE_L") (class "Default")
      (node (ref "LEFT") (pin "IR_SENSE") (pinfunction "IR_SENS_IR_SENSE") (pintype "bidirectional"))
      (node (ref "R20") (pin "2") (pinfunction "2_2") (pintype "passive"))
      (node (ref "U6") (pin "37") (pinfunction "(ADC0/PCINT0)PA0_37") (pintype "bidirectional"))
    )
    (net (code "27") (name "IR_SENSE_R") (class "Default")
      (node (ref "R19") (pin "1") (pinfunction "1_1") (pintype "passive"))
      (node (ref "RIGHT") (pin "IR_SENSE") (pinfunction "IR_SENS_IR_SENSE") (pintype "bidirectional"))
      (node (ref "U6") (pin "35") (pinfunction "(ADC2/PCINT2)PA2_35") (pintype "bidirectional"))
    )
    (net (code "28") (name "MISO") (class "Default")
      (node (ref "JP3") (pin "1") (pinfunction "1_1") (pintype "passive"))
      (node (ref "U6") (pin "2") (pinfunction "(MISO/PCINT14)PB6_2") (pintype "bidirectional"))
    )
    (net (code "29") (name "MOSI") (class "Default")
      (node (ref "JP3") (pin "4") (pinfunction "4_4") (pintype "passive"))
      (node (ref "U6") (pin "1") (pinfunction "(MOSI/PCINT13)PB5_1") (pintype "bidirectional"))
    )
    (net (code "30") (name "NETWORK_LED") (class "Default")
      (node (ref "LED5") (pin "A") (pinfunction "A_A") (pintype "passive"))
      (node (ref "U6") (pin "22") (pinfunction "(TMS/PCINT19)PC3_22") (pintype "bidirectional"))
    )
    (net (code "31") (name "Net-(C5-Pad2)") (class "Default")
      (node (ref "C5") (pin "2") (pinfunction "2_2") (pintype "passive"))
      (node (ref "R5") (pin "2") (pinfunction "2_2") (pintype "passive"))
    )
    (net (code "32") (name "Net-(C6-Pad1)") (class "Default")
      (node (ref "C6") (pin "1") (pinfunction "1_1") (pintype "passive"))
      (node (ref "R6") (pin "2") (pinfunction "2_2") (pintype "passive"))
    )
    (net (code "33") (name "Net-(C13-Pad2)") (class "Default")
      (node (ref "C13") (pin "2") (pinfunction "2_2") (pintype "passive"))
      (node (ref "JP2") (pin "6") (pinfunction "6_6") (pintype "passive"))
    )
    (net (code "34") (name "Net-(JP2-Pad3)") (class "Default")
      (node (ref "JP2") (pin "3") (pinfunction "3_3") (pintype "passive"))
      (node (ref "SJ1") (pin "1") (pinfunction "1_1") (pintype "passive"))
    )
    (net (code "35") (name "Net-(LED1-PadC)") (class "Default")
      (node (ref "LED1") (pin "C") (pinfunction "C_C") (pintype "passive"))
      (node (ref "R9") (pin "2") (pinfunction "2_2") (pintype "passive"))
    )
    (net (code "36") (name "Net-(LED3-PadC)") (class "Default")
      (node (ref "LED3") (pin "C") (pinfunction "C_C") (pintype "passive"))
      (node (ref "R26") (pin "2") (pinfunction "2_2") (pintype "passive"))
    )
    (net (code "37") (name "Net-(LED4-PadC)") (class "Default")
      (node (ref "LED4") (pin "C") (pinfunction "C_C") (pintype "passive"))
      (node (ref "R27") (pin "2") (pinfunction "2_2") (pintype "passive"))
    )
    (net (code "38") (name "Net-(LED5-PadC)") (class "Default")
      (node (ref "LED5") (pin "C") (pinfunction "C_C") (pintype "passive"))
      (node (ref "R28") (pin "2") (pinfunction "2_2") (pintype "passive"))
    )
    (net (code "39") (name "Net-(LEFT-PadP_EMIT)") (class "Default")
      (node (ref "LEFT") (pin "P_EMIT") (pinfunction "P_EMIT_P_EMIT") (pintype "bidirectional"))
      (node (ref "R17") (pin "1") (pinfunction "1_1") (pintype "passive"))
    )
    (net (code "40") (name "Net-(R17-Pad2)") (class "Default")
      (node (ref "R17") (pin "2") (pinfunction "2_2") (pintype "passive"))
      (node (ref "T1") (pin "C") (pinfunction "C_C") (pintype "passive"))
    )
    (net (code "41") (name "Net-(R18-Pad2)") (class "Default")
      (node (ref "R18") (pin "2") (pinfunction "2_2") (pintype "passive"))
      (node (ref "T1") (pin "B") (pinfunction "B_B") (pintype "passive"))
    )
    (net (code "42") (name "Net-(R25-Pad1)") (class "Default")
      (node (ref "R25") (pin "1") (pinfunction "1_1") (pintype "passive"))
      (node (ref "T2") (pin "B") (pinfunction "B_B") (pintype "passive"))
    )
    (net (code "43") (name "Net-(U1-IN)") (class "Default")
      (node (ref "S1") (pin "3") (pinfunction "3_3") (pintype "passive"))
      (node (ref "S1") (pin "4") (pinfunction "4_4") (pintype "passive"))
      (node (ref "U1") (pin "1") (pinfunction "IN_1") (pintype "input"))
    )
    (net (code "44") (name "Net-(U2-1IN+)") (class "Default")
      (node (ref "R1") (pin "1") (pinfunction "1_1") (pintype "passive"))
      (node (ref "R2") (pin "2") (pinfunction "2_2") (pintype "passive"))
      (node (ref "U2") (pin "3") (pinfunction "1IN+_3") (pintype "input"))
    )
    (net (code "45") (name "Net-(U3-FB)") (class "Default")
      (node (ref "C5") (pin "1") (pinfunction "1_1") (pintype "passive"))
      (node (ref "R6") (pin "1") (pinfunction "1_1") (pintype "passive"))
      (node (ref "R7") (pin "2") (pinfunction "2_2") (pintype "passive"))
      (node (ref "R8") (pin "1") (pinfunction "1_1") (pintype "passive"))
      (node (ref "U3") (pin "11") (pinfunction "FB_11") (pintype "bidirectional"))
    )
    (net (code "46") (name "Net-(U3-RT)") (class "Default")
      (node (ref "R4") (pin "2") (pinfunction "2_2") (pintype "passive"))
      (node (ref "U3") (pin "1") (pinfunction "RT_1") (pintype "bidirectional"))
    )
    (net (code "47") (name "Net-(U3-SW1)") (class "Default")
      (node (ref "L1") (pin "P$1") (pinfunction "P$1_P$1") (pintype "passive"))
      (node (ref "U3") (pin "4") (pinfunction "SW1_4") (pintype "power_in"))
    )
    (net (code "48") (name "Net-(U3-SW2)") (class "Default")
      (node (ref "L1") (pin "P$2") (pinfunction "P$2_P$2") (pintype "passive"))
      (node (ref "U3") (pin "6") (pinfunction "SW2_6") (pintype "power_in"))
    )
    (net (code "49") (name "Net-(U3-VC)") (class "Default")
      (node (ref "R5") (pin "1") (pinfunction "1_1") (pintype "passive"))
      (node (ref "U3") (pin "12") (pinfunction "VC_12") (pintype "bidirectional"))
    )
    (net (code "50") (name "Net-(U4-2IN-)") (class "Default")
      (node (ref "R14") (pin "1") (pinfunction "1_1") (pintype "passive"))
      (node (ref "R15") (pin "2") (pinfunction "2_2") (pintype "passive"))
      (node (ref "U4") (pin "6") (pinfunction "2IN-_6") (pintype "input"))
    )
    (net (code "51") (name "Net-(U5-REXT)") (class "Default")
      (node (ref "R21") (pin "1") (pinfunction "1_1") (pintype "passive"))
      (node (ref "U5") (pin "1") (pinfunction "REXT_1") (pintype "bidirectional"))
    )
    (net (code "52") (name "Net-(U6-AREF)") (class "Default")
      (node (ref "C14") (pin "1") (pinfunction "1_1") (pintype "passive"))
      (node (ref "U6") (pin "29") (pinfunction "AREF_29") (pintype "power_in"))
    )
    (net (code "53") (name "Net-(U6-XTAL1)") (class "Default")
      (node (ref "U6") (pin "8") (pinfunction "XTAL1_8") (pintype "input"))
      (node (ref "Y1") (pin "3") (pinfunction "3_3") (pintype "passive"))
    )
    (net (code "54") (name "Net-(U6-XTAL2)") (class "Default")
      (node (ref "U6") (pin "7") (pinfunction "XTAL2_7") (pintype "output"))
      (node (ref "Y1") (pin "1") (pinfunction "1_1") (pintype "passive"))
    )
    (net (code "55") (name "Net-(U7-RESET)") (class "Default")
      (node (ref "T2") (pin "C") (pinfunction "C_C") (pintype "passive"))
      (node (ref "U7") (pin "5") (pinfunction "RESET_5") (pintype "input"))
    )
    (net (code "56") (name "PGND") (class "Default")
      (node (ref "C3") (pin "2") (pinfunction "2_2") (pintype "passive"))
      (node (ref "C4") (pin "2") (pinfunction "2_2") (pintype "passive"))
      (node (ref "C7") (pin "2") (pinfunction "2_2") (pintype "passive"))
      (node (ref "C8") (pin "2") (pinfunction "2_2") (pintype "passive"))
      (node (ref "JP1") (pin "GND@1") (pinfunction "-1_GND@1") (pintype "power_in"))
      (node (ref "JP1") (pin "GND@2") (pinfunction "-2_GND@2") (pintype "power_in"))
      (node (ref "JP1") (pin "GND@3") (pinfunction "-3_GND@3") (pintype "power_in"))
      (node (ref "JP1") (pin "GND@4") (pinfunction "-4_GND@4") (pintype "power_in"))
      (node (ref "JP1") (pin "GND@5") (pinfunction "-5_GND@5") (pintype "power_in"))
      (node (ref "JP1") (pin "GND@6") (pinfunction "-6_GND@6") (pintype "power_in"))
      (node (ref "R10") (pin "1") (pinfunction "1_1") (pintype "passive"))
      (node (ref "R11") (pin "2") (pinfunction "2_2") (pintype "passive"))
      (node (ref "R4") (pin "1") (pinfunction "1_1") (pintype "passive"))
      (node (ref "R7") (pin "1") (pinfunction "1_1") (pintype "passive"))
      (node (ref "TP3") (pin "P$1") (pinfunction "1_P$1") (pintype "bidirectional"))
      (node (ref "TP9") (pin "P$1") (pinfunction "1_P$1") (pintype "bidirectional"))
      (node (ref "U3") (pin "13") (pinfunction "PGND2_13") (pintype "power_in"))
      (node (ref "U3") (pin "2") (pinfunction "SGND_2") (pintype "power_in"))
      (node (ref "U3") (pin "3") (pinfunction "MODE/SYNC_3") (pintype "bidirectional"))
      (node (ref "U3") (pin "5") (pinfunction "PGND1_5") (pintype "power_in"))
    )
    (net (code "57") (name "PROX_EMIT") (class "Default")
      (node (ref "R18") (pin "1") (pinfunction "1_1") (pintype "passive"))
      (node (ref "U6") (pin "41") (pinfunction "(CLKO/T1/PCINT9)PB1_41") (pintype "bidirectional"))
    )
    (net (code "58") (name "PROX_SENSE") (class "Default")
      (node (ref "R16") (pin "1") (pinfunction "1_1") (pintype "passive"))
      (node (ref "TP8") (pin "P$1") (pinfunction "1_P$1") (pintype "bidirectional"))
      (node (ref "U4") (pin "7") (pinfunction "2OUT_7") (pintype "output"))
      (node (ref "U6") (pin "15") (pinfunction "(OC2B/ICP/PCINT30)PD6_15") (pintype "bidirectional"))
    )
    (net (code "59") (name "PROX_SENSE_A") (class "Default")
      (node (ref "LEFT") (pin "P_SENS") (pinfunction "P_SENS_P_SENS") (pintype "bidirectional"))
      (node (ref "R12") (pin "2") (pinfunction "2_2") (pintype "passive"))
      (node (ref "R13") (pin "1") (pinfunction "1_1") (pintype "passive"))
      (node (ref "TP6") (pin "P$1") (pinfunction "1_P$1") (pintype "bidirectional"))
    )
    (net (code "60") (name "PROX_SENSE_S") (class "Default")
      (node (ref "C9") (pin "1") (pinfunction "1_1") (pintype "passive"))
      (node (ref "R13") (pin "2") (pinfunction "2_2") (pintype "passive"))
      (node (ref "TP7") (pin "P$1") (pinfunction "1_P$1") (pintype "bidirectional"))
      (node (ref "U4") (pin "5") (pinfunction "2IN+_5") (pintype "input"))
    )
    (net (code "61") (name "PWR_CLEAR") (class "Default")
      (node (ref "R3") (pin "2") (pinfunction "2_2") (pintype "passive"))
      (node (ref "U1") (pin "3") (pinfunction "CLEAR_3") (pintype "input"))
      (node (ref "U6") (pin "43") (pinfunction "(OC0A/AIN1/PCINT11)PB3_43") (pintype "bidirectional"))
    )
    (net (code "62") (name "PWR_ENABLE") (class "Default")
      (node (ref "U1") (pin "5") (pinfunction "OUT_5") (pintype "output"))
      (node (ref "U3") (pin "10") (pinfunction "~{SHDN}_10") (pintype "bidirectional"))
    )
    (net (code "63") (name "RED_L") (class "Default")
      (node (ref "RGB_LED_L") (pin "C1") (pinfunction "C_C1") (pintype "passive"))
      (node (ref "U5") (pin "14") (pinfunction "/OUT7_14") (pintype "bidirectional"))
    )
    (net (code "64") (name "RED_M") (class "Default")
      (node (ref "RGB_LED_M") (pin "C1") (pinfunction "C_C1") (pintype "passive"))
      (node (ref "U5") (pin "11") (pinfunction "/OUT4_11") (pintype "bidirectional"))
    )
    (net (code "65") (name "RED_R") (class "Default")
      (node (ref "RGB_LED_R") (pin "C1") (pinfunction "C_C1") (pintype "passive"))
      (node (ref "U5") (pin "7") (pinfunction "/OUT1_7") (pintype "bidirectional"))
    )
    (net (code "66") (name "RED_T") (class "Default")
      (node (ref "LED2") (pin "1") (pinfunction "CR_1") (pintype "bidirectional"))
      (node (ref "U5") (pin "23") (pinfunction "/OUT15_23") (pintype "bidirectional"))
    )
    (net (code "67") (name "RST") (class "Default")
      (node (ref "C13") (pin "1") (pinfunction "1_1") (pintype "passive"))
      (node (ref "JP3") (pin "5") (pinfunction "5_5") (pintype "passive"))
      (node (ref "R24") (pin "1") (pinfunction "1_1") (pintype "passive"))
      (node (ref "U5") (pin "25") (pinfunction "/RESET_25") (pintype "bidirectional"))
      (node (ref "U6") (pin "4") (pinfunction "~{RESET}_4") (pintype "input"))
    )
    (net (code "68") (name "RXD") (class "Default")
      (node (ref "JP2") (pin "4") (pinfunction "4_4") (pintype "passive"))
      (node (ref "U6") (pin "9") (pinfunction "(RXD0/PCINT24)PD0_9") (pintype "bidirectional"))
    )
    (net (code "69") (name "SCK") (class "Default")
      (node (ref "JP3") (pin "3") (pinfunction "3_3") (pintype "passive"))
      (node (ref "U6") (pin "3") (pinfunction "(SCK/PCINT15)PB7_3") (pintype "bidirectional"))
    )
    (net (code "70") (name "TXD") (class "Default")
      (node (ref "JP2") (pin "5") (pinfunction "5_5") (pintype "passive"))
      (node (ref "U6") (pin "10") (pinfunction "(TXD0/PCINT25)PD1_10") (pintype "bidirectional"))
    )
    (net (code "71") (name "VBATT") (class "Default")
      (node (ref "C1") (pin "1") (pinfunction "1_1") (pintype "passive"))
      (node (ref "C3") (pin "1") (pinfunction "1_1") (pintype "passive"))
      (node (ref "C4") (pin "1") (pinfunction "1_1") (pintype "passive"))
      (node (ref "JP1") (pin "PWR@1") (pinfunction "+1_PWR@1") (pintype "power_in"))
      (node (ref "JP1") (pin "PWR@2") (pinfunction "+2_PWR@2") (pintype "power_in"))
      (node (ref "JP1") (pin "PWR@3") (pinfunction "+3_PWR@3") (pintype "power_in"))
      (node (ref "R1") (pin "2") (pinfunction "2_2") (pintype "passive"))
      (node (ref "SJ1") (pin "2") (pinfunction "2_2") (pintype "passive"))
      (node (ref "TP10") (pin "P$1") (pinfunction "1_P$1") (pintype "bidirectional"))
      (node (ref "U1") (pin "6") (pinfunction "VCC_6") (pintype "power_in"))
      (node (ref "U3") (pin "8") (pinfunction "VIN1_8") (pintype "input"))
      (node (ref "U3") (pin "9") (pinfunction "VIN2_9") (pintype "input"))
    )
    (net (code "72") (name "VBATT_SENSE") (class "Default")
      (node (ref "U2") (pin "1") (pinfunction "1OUT_1") (pintype "output"))
      (node (ref "U2") (pin "2") (pinfunction "1IN-_2") (pintype "input"))
      (node (ref "U6") (pin "36") (pinfunction "(ADC1/PCINT1)PA1_36") (pintype "bidirectional"))
    )
    (net (code "73") (name "VCC") (class "Default")
      (node (ref "C11") (pin "1") (pinfunction "1_1") (pintype "passive"))
      (node (ref "C12") (pin "1") (pinfunction "1_1") (pintype "passive"))
      (node (ref "C16") (pin "1") (pinfunction "1_1") (pintype "passive"))
      (node (ref "C17") (pin "1") (pinfunction "1_1") (pintype "passive"))
      (node (ref "C18") (pin "1") (pinfunction "1_1") (pintype "passive"))
      (node (ref "C19") (pin "1") (pinfunction "1_1") (pintype "passive"))
      (node (ref "C6") (pin "2") (pinfunction "2_2") (pintype "passive"))
      (node (ref "C7") (pin "1") (pinfunction "1_1") (pintype "passive"))
      (node (ref "C8") (pin "1") (pinfunction "1_1") (pintype "passive"))
      (node (ref "JP3") (pin "2") (pinfunction "2_2") (pintype "passive"))
      (node (ref "JP4") (pin "14") (pinfunction "14_14") (pintype "passive"))
      (node (ref "L2") (pin "1") (pinfunction "P$1_1") (pintype "passive"))
      (node (ref "LED1") (pin "A") (pinfunction "A_A") (pintype "passive"))
      (node (ref "LED2") (pin "2") (pinfunction "A_2") (pintype "bidirectional"))
      (node (ref "LED3") (pin "A") (pinfunction "A_A") (pintype "passive"))
      (node (ref "LED4") (pin "A") (pinfunction "A_A") (pintype "passive"))
      (node (ref "LEFT") (pin "VCC") (pinfunction "VCC_VCC") (pintype "bidirectional"))
      (node (ref "R22") (pin "2") (pinfunction "2_2") (pintype "passive"))
      (node (ref "R23") (pin "2") (pinfunction "2_2") (pintype "passive"))
      (node (ref "R24") (pin "2") (pinfunction "2_2") (pintype "passive"))
      (node (ref "R8") (pin "2") (pinfunction "2_2") (pintype "passive"))
      (node (ref "RGB_LED_L") (pin "A1") (pinfunction "A_A1") (pintype "passive"))
      (node (ref "RGB_LED_L") (pin "A2") (pinfunction "A_A2") (pintype "passive"))
      (node (ref "RGB_LED_L") (pin "A3") (pinfunction "A_A3") (pintype "passive"))
      (node (ref "RGB_LED_M") (pin "A1") (pinfunction "A_A1") (pintype "passive"))
      (node (ref "RGB_LED_M") (pin "A2") (pinfunction "A_A2") (pintype "passive"))
      (node (ref "RGB_LED_M") (pin "A3") (pinfunction "A_A3") (pintype "passive"))
      (node (ref "RGB_LED_R") (pin "A1") (pinfunction "A_A1") (pintype "passive"))
      (node (ref "RGB_LED_R") (pin "A2") (pinfunction "A_A2") (pintype "passive"))
      (node (ref "RGB_LED_R") (pin "A3") (pinfunction "A_A3") (pintype "passive"))
      (node (ref "RIGHT") (pin "VCC") (pinfunction "VCC_VCC") (pintype "bidirectional"))
      (node (ref "TP1") (pin "P$1") (pinfunction "1_P$1") (pintype "bidirectional"))
      (node (ref "U3") (pin "7") (pinfunction "VOUT_7") (pintype "power_in"))
      (node (ref "U5") (pin "28") (pinfunction "VCC_28") (pintype "bidirectional"))
      (node (ref "U6") (pin "17") (pinfunction "VCC_17") (pintype "power_in"))
      (node (ref "U6") (pin "38") (pinfunction "VCC_38") (pintype "power_in"))
      (node (ref "U6") (pin "5") (pinfunction "VCC_5") (pintype "power_in"))
      (node (ref "U7") (pin "1") (pinfunction "VDD_1") (pintype "power_in"))
    )
    (net (code "74") (name "XBEE_CTS") (class "Default")
      (node (ref "U6") (pin "14") (pinfunction "(OC1A/PCINT29)PD5_14") (pintype "bidirectional"))
      (node (ref "U7") (pin "12") (pinfunction "CTS_12") (pintype "output"))
    )
    (net (code "75") (name "XBEE_NET_0") (class "Default")
      (node (ref "S2") (pin "4") (pinfunction "4_4") (pintype "passive"))
      (node (ref "U6") (pin "44") (pinfunction "(OC0B/~{SS}/PCINT12)PB4_44") (pintype "bidirectional"))
    )
    (net (code "76") (name "XBEE_NET_1") (class "Default")
      (node (ref "S2") (pin "3") (pinfunction "3_3") (pintype "passive"))
      (node (ref "U6") (pin "42") (pinfunction "(INT2/AIN0/PCINT10)PB2_42") (pintype "bidirectional"))
    )
    (net (code "77") (name "XBEE_RST") (class "Default")
      (node (ref "R25") (pin "2") (pinfunction "2_2") (pintype "passive"))
      (node (ref "U6") (pin "16") (pinfunction "(OC2A/PCINT31)PD7_16") (pintype "bidirectional"))
    )
    (net (code "78") (name "XBEE_RTS") (class "Default")
      (node (ref "U6") (pin "21") (pinfunction "(TCK/PCINT18)PC2_21") (pintype "bidirectional"))
      (node (ref "U7") (pin "16") (pinfunction "RTS_16") (pintype "input"))
    )
    (net (code "79") (name "XBEE_RXD") (class "Default")
      (node (ref "R27") (pin "1") (pinfunction "1_1") (pintype "passive"))
      (node (ref "U6") (pin "11") (pinfunction "(RXD1/INT0/PCINT26)PD2_11") (pintype "bidirectional"))
      (node (ref "U7") (pin "2") (pinfunction "DOUT_2") (pintype "output"))
    )
    (net (code "80") (name "XBEE_TXD") (class "Default")
      (node (ref "R26") (pin "1") (pinfunction "1_1") (pintype "passive"))
      (node (ref "U6") (pin "12") (pinfunction "(TXD1/INT1/PCINT27)PD3_12") (pintype "bidirectional"))
      (node (ref "U7") (pin "3") (pinfunction "DIN_3") (pintype "input"))
    )
    (net (code "81") (name "XBEE_WAKE") (class "Default")
      (node (ref "U6") (pin "13") (pinfunction "(XCK1/OC1B/PCINT28)PD4_13") (pintype "bidirectional"))
      (node (ref "U7") (pin "9") (pinfunction "DTR_9") (pintype "bidirectional"))
    )
    (net (code "82") (name "unconnected-(JP2-Pad2)") (class "Default")
      (node (ref "JP2") (pin "2") (pinfunction "2_2") (pintype "passive"))
    )
    (net (code "83") (name "unconnected-(RIGHT-PadP_EMIT)") (class "Default")
      (node (ref "RIGHT") (pin "P_EMIT") (pinfunction "P_EMIT_P_EMIT") (pintype "bidirectional"))
    )
    (net (code "84") (name "unconnected-(RIGHT-PadP_SENS)") (class "Default")
      (node (ref "RIGHT") (pin "P_SENS") (pinfunction "P_SENS_P_SENS") (pintype "bidirectional"))
    )
    (net (code "85") (name "unconnected-(U1-~{OUT}-Pad4)") (class "Default")
      (node (ref "U1") (pin "4") (pinfunction "~{OUT}_4") (pintype "output"))
    )
    (net (code "86") (name "unconnected-(U2-2OUT-Pad7)") (class "Default")
      (node (ref "U2") (pin "7") (pinfunction "2OUT_7") (pintype "output"))
    )
    (net (code "87") (name "unconnected-(U4-1IN+-Pad3)") (class "Default")
      (node (ref "U4") (pin "3") (pinfunction "1IN+_3") (pintype "input"))
    )
    (net (code "88") (name "unconnected-(U4-1IN--Pad2)") (class "Default")
      (node (ref "U4") (pin "2") (pinfunction "1IN-_2") (pintype "input"))
    )
    (net (code "89") (name "unconnected-(U4-1OUT-Pad1)") (class "Default")
      (node (ref "U4") (pin "1") (pinfunction "1OUT_1") (pintype "output"))
    )
    (net (code "90") (name "unconnected-(U6-(ADC3{slash}PCINT3)PA3-Pad34)") (class "Default")
      (node (ref "U6") (pin "34") (pinfunction "(ADC3/PCINT3)PA3_34") (pintype "bidirectional"))
    )
    (net (code "91") (name "unconnected-(U6-(XCK0{slash}T0{slash}PCINT8)PB0-Pad40)") (class "Default")
      (node (ref "U6") (pin "40") (pinfunction "(XCK0/T0/PCINT8)PB0_40") (pintype "bidirectional"))
    )
    (net (code "92") (name "unconnected-(U7-DIO0-Pad20)") (class "Default")
      (node (ref "U7") (pin "20") (pinfunction "DIO0_20") (pintype "bidirectional"))
    )
    (net (code "93") (name "unconnected-(U7-DIO1-Pad19)") (class "Default")
      (node (ref "U7") (pin "19") (pinfunction "DIO1_19") (pintype "bidirectional"))
    )
    (net (code "94") (name "unconnected-(U7-DIO2-Pad18)") (class "Default")
      (node (ref "U7") (pin "18") (pinfunction "DIO2_18") (pintype "bidirectional"))
    )
    (net (code "95") (name "unconnected-(U7-DIO3-Pad17)") (class "Default")
      (node (ref "U7") (pin "17") (pinfunction "DIO3_17") (pintype "bidirectional"))
    )
    (net (code "96") (name "unconnected-(U7-DIO4-Pad11)") (class "Default")
      (node (ref "U7") (pin "11") (pinfunction "DIO4_11") (pintype "bidirectional"))
    )
    (net (code "97") (name "unconnected-(U7-DIO5-Pad15)") (class "Default")
      (node (ref "U7") (pin "15") (pinfunction "DIO5_15") (pintype "bidirectional"))
    )
    (net (code "98") (name "unconnected-(U7-DIO9-Pad13)") (class "Default")
      (node (ref "U7") (pin "13") (pinfunction "DIO9_13") (pintype "bidirectional"))
    )
    (net (code "99") (name "unconnected-(U7-DIO11-Pad7)") (class "Default")
      (node (ref "U7") (pin "7") (pinfunction "DIO11_7") (pintype "bidirectional"))
    )
    (net (code "100") (name "unconnected-(U7-DIO12-Pad4)") (class "Default")
      (node (ref "U7") (pin "4") (pinfunction "DIO12_4") (pintype "bidirectional"))
    )
    (net (code "101") (name "unconnected-(U7-RES-Pad8)") (class "Default")
      (node (ref "U7") (pin "8") (pinfunction "RES_8") (pintype "bidirectional"))
    )
    (net (code "102") (name "unconnected-(U7-RES-Pad14)") (class "Default")
      (node (ref "U7") (pin "14") (pinfunction "RES_14") (pintype "bidirectional"))
    )
    (net (code "103") (name "unconnected-(U7-RSSI-Pad6)") (class "Default")
      (node (ref "U7") (pin "6") (pinfunction "RSSI_6") (pintype "bidirectional"))
    )
  )
)
